# Power.net
KiCad netlist of a schematic drawn in Altium Designer
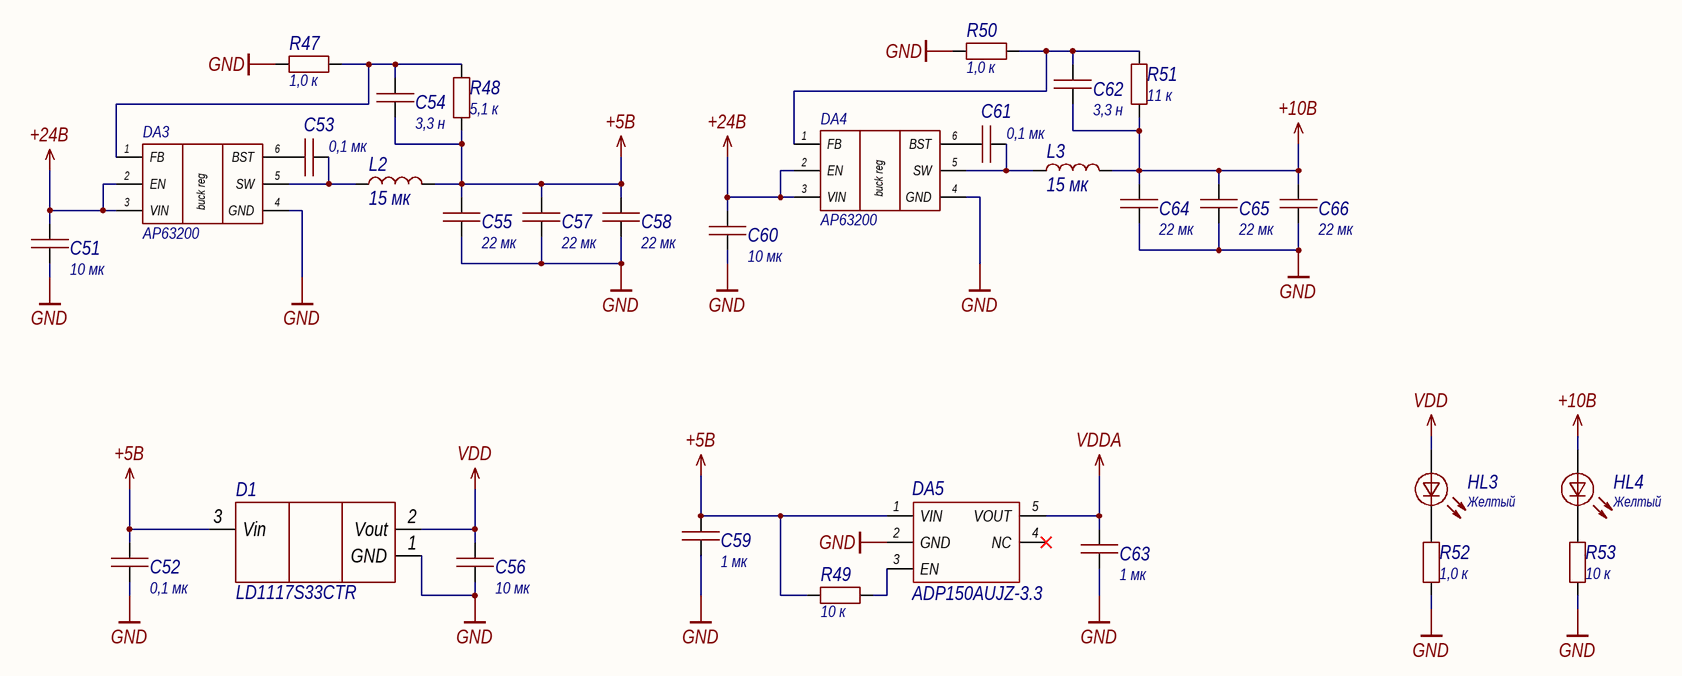
[diagram p0: Power.SchDoc]

(export (version "E")
  (design (tool "Eeschema 10.0.6"))
  (components
    (comp (ref "C51")
      (value "10 мк")
      (footprint "1210C")
      (description "Конденсатор 1210C ёмкостью 10 мк 10%, 35 В, X7R")
      (fields (field (name "PART NUMBER") "Capacitor_10u_10_35V_X7R_1210C") (field (name "TOLERANCE") "10%"))
      (libsource (lib "Hydrolib") (part "Capacitor"))
    )
    (comp (ref "C52")
      (value "0,1 мк")
      (footprint "0603C")
      (description "Конденсатор 0603C ёмкостью 0,1 мк 10%, 50 В, X7R")
      (fields (field (name "PART NUMBER") "Capacitor_0,1u_10_50V_X7R_0603C") (field (name "TOLERANCE") "10%"))
      (libsource (lib "Hydrolib") (part "Capacitor"))
    )
    (comp (ref "C53")
      (value "0,1 мк")
      (footprint "0603C")
      (description "Конденсатор 0603C ёмкостью 0,1 мк 10%, 50 В, X7R")
      (fields (field (name "PART NUMBER") "Capacitor_0,1u_10_50V_X7R_0603C") (field (name "TOLERANCE") "10%"))
      (libsource (lib "Hydrolib") (part "Capacitor"))
    )
    (comp (ref "C54")
      (value "3,3 н")
      (footprint "0603C")
      (description "Конденсатор 0603C ёмкостью 3,3 н 5%, 50 В, NP0")
      (fields
        (field (name "PART NUMBER") "Capacitor_3.3n_5_50V_NP0_0603C")
        (field (name "TOLERANCE") "5%")
        (field (name "АВТОР") "glebmih")
      )
      (libsource (lib "Hydrolib") (part "Capacitor"))
    )
    (comp (ref "C55")
      (value "22 мк")
      (footprint "1210C")
      (description "Конденсатор 1210C ёмкостью 22 мк 10%, 25 В, X7R")
      (fields (field (name "PART NUMBER") "Capacitor_22u_10_25V_X7R_1210C") (field (name "TOLERANCE") "10%"))
      (libsource (lib "Hydrolib") (part "Capacitor"))
    )
    (comp (ref "C56")
      (value "10 мк")
      (footprint "1210C")
      (description "Конденсатор 1210C ёмкостью 10 мк 10%, 35 В, X7R")
      (fields (field (name "PART NUMBER") "Capacitor_10u_10_35V_X7R_1210C") (field (name "TOLERANCE") "10%"))
      (libsource (lib "Hydrolib") (part "Capacitor"))
    )
    (comp (ref "C57")
      (value "22 мк")
      (footprint "1210C")
      (description "Конденсатор 1210C ёмкостью 22 мк 10%, 25 В, X7R")
      (fields (field (name "PART NUMBER") "Capacitor_22u_10_25V_X7R_1210C") (field (name "TOLERANCE") "10%"))
      (libsource (lib "Hydrolib") (part "Capacitor"))
    )
    (comp (ref "C58")
      (value "22 мк")
      (footprint "1210C")
      (description "Конденсатор 1210C ёмкостью 22 мк 10%, 25 В, X7R")
      (fields (field (name "PART NUMBER") "Capacitor_22u_10_25V_X7R_1210C") (field (name "TOLERANCE") "10%"))
      (libsource (lib "Hydrolib") (part "Capacitor"))
    )
    (comp (ref "C59")
      (value "1 мк")
      (footprint "0603C")
      (description "Конденсатор 0603C ёмкостью 1 мк 10%, 25 В, X7R")
      (fields (field (name "PART NUMBER") "Capacitor_1u_10_25V_X7R_0603C") (field (name "TOLERANCE") "10%"))
      (libsource (lib "Hydrolib") (part "Capacitor"))
    )
    (comp (ref "C60")
      (value "10 мк")
      (footprint "1210C")
      (description "Конденсатор 1210C ёмкостью 10 мк 10%, 35 В, X7R")
      (fields (field (name "PART NUMBER") "Capacitor_10u_10_35V_X7R_1210C") (field (name "TOLERANCE") "10%"))
      (libsource (lib "Hydrolib") (part "Capacitor"))
    )
    (comp (ref "C61")
      (value "0,1 мк")
      (footprint "0603C")
      (description "Конденсатор 0603C ёмкостью 0,1 мк 10%, 50 В, X7R")
      (fields (field (name "PART NUMBER") "Capacitor_0,1u_10_50V_X7R_0603C") (field (name "TOLERANCE") "10%"))
      (libsource (lib "Hydrolib") (part "Capacitor"))
    )
    (comp (ref "C62")
      (value "3,3 н")
      (footprint "0603C")
      (description "Конденсатор 0603C ёмкостью 3,3 н 5%, 50 В, NP0")
      (fields
        (field (name "PART NUMBER") "Capacitor_3.3n_5_50V_NP0_0603C")
        (field (name "TOLERANCE") "5%")
        (field (name "АВТОР") "glebmih")
      )
      (libsource (lib "Hydrolib") (part "Capacitor"))
    )
    (comp (ref "C63")
      (value "1 мк")
      (footprint "0603C")
      (description "Конденсатор 0603C ёмкостью 1 мк 10%, 25 В, X7R")
      (fields (field (name "PART NUMBER") "Capacitor_1u_10_25V_X7R_0603C") (field (name "TOLERANCE") "10%"))
      (libsource (lib "Hydrolib") (part "Capacitor"))
    )
    (comp (ref "C64")
      (value "22 мк")
      (footprint "1210C")
      (description "Конденсатор 1210C ёмкостью 22 мк 10%, 25 В, X7R")
      (fields (field (name "PART NUMBER") "Capacitor_22u_10_25V_X7R_1210C") (field (name "TOLERANCE") "10%"))
      (libsource (lib "Hydrolib") (part "Capacitor"))
    )
    (comp (ref "C65")
      (value "22 мк")
      (footprint "1210C")
      (description "Конденсатор 1210C ёмкостью 22 мк 10%, 25 В, X7R")
      (fields (field (name "PART NUMBER") "Capacitor_22u_10_25V_X7R_1210C") (field (name "TOLERANCE") "10%"))
      (libsource (lib "Hydrolib") (part "Capacitor"))
    )
    (comp (ref "C66")
      (value "22 мк")
      (footprint "1210C")
      (description "Конденсатор 1210C ёмкостью 22 мк 10%, 25 В, X7R")
      (fields (field (name "PART NUMBER") "Capacitor_22u_10_25V_X7R_1210C") (field (name "TOLERANCE") "10%"))
      (libsource (lib "Hydrolib") (part "Capacitor"))
    )
    (comp (ref "D1")
      (value "LD1117S33CTR")
      (footprint "SOT223")
      (description "Линейный стабилизатор напряжения")
      (libsource (lib "Hydrolib") (part "LD1117S33CTR"))
    )
    (comp (ref "DA3")
      (value "AP63200")
      (footprint "TSOT26")
      (description "DC-DC понижающий преобразователь, Vin: 3.8 - 40 В, adj, 2 А")
      (libsource (lib "Hydrolib") (part "AP63200"))
    )
    (comp (ref "DA4")
      (value "AP63200")
      (footprint "TSOT26")
      (description "DC-DC понижающий преобразователь, Vin: 3.8 - 40 В, adj, 2 А")
      (libsource (lib "Hydrolib") (part "AP63200"))
    )
    (comp (ref "DA5")
      (value "ADP150AUJZ-3.3")
      (footprint "SOT23-5")
      (description "Стабилизатор напряжения 3.3В 150мА")
      (fields (field (name "АВТОР") "glebmih"))
      (libsource (lib "Hydrolib") (part "ADP150AUJZ-3.3"))
    )
    (comp (ref "HL3")
      (value "Желтый")
      (footprint "0805D")
      (description "Светодиод")
      (fields (field (name "PART NUMBER") "LED"))
      (libsource (lib "Hydrolib") (part "LED"))
    )
    (comp (ref "HL4")
      (value "Желтый")
      (footprint "0805D")
      (description "Светодиод")
      (fields (field (name "PART NUMBER") "LED"))
      (libsource (lib "Hydrolib") (part "LED"))
    )
    (comp (ref "L2")
      (value "15 мк")
      (footprint "SP43")
      (description "Индуктивность на 15 мкГн, номинальный ток 1,3 А")
      (fields (field (name "PART NUMBER") "SP43-150K"))
      (libsource (lib "Hydrolib") (part "Inductance"))
    )
    (comp (ref "L3")
      (value "15 мк")
      (footprint "SP43")
      (description "Индуктивность на 15 мкГн, номинальный ток 1,3 А")
      (fields (field (name "PART NUMBER") "SP43-150K"))
      (libsource (lib "Hydrolib") (part "Inductance"))
    )
    (comp (ref "R47")
      (value "1,0 к")
      (footprint "0603R")
      (description "Резистор номиналом 1,0 кОм 1%")
      (fields (field (name "PART NUMBER") "Resistor_1.0k_1_0603") (field (name "TOLERANCE") "1%"))
      (libsource (lib "") (part "Resistor_1"))
    )
    (comp (ref "R48")
      (value "5,1 к")
      (footprint "0603R")
      (description "Резистор номиналом 5,1 кОм 1%")
      (fields (field (name "PART NUMBER") "Resistor_5.1k_1_0603") (field (name "TOLERANCE") "1%"))
      (libsource (lib "Hydrolib") (part "Resistor"))
    )
    (comp (ref "R49")
      (value "10 к")
      (footprint "0603R")
      (description "Резистор номиналом 10 кОм 1%")
      (fields (field (name "PART NUMBER") "Resistor_10k_1_0603") (field (name "TOLERANCE") "1%"))
      (libsource (lib "") (part "Resistor_2"))
    )
    (comp (ref "R50")
      (value "1,0 к")
      (footprint "0603R")
      (description "Резистор номиналом 1,0 кОм 1%")
      (fields (field (name "PART NUMBER") "Resistor_1.0k_1_0603") (field (name "TOLERANCE") "1%"))
      (libsource (lib "") (part "Resistor_1"))
    )
    (comp (ref "R51")
      (value "11 к")
      (footprint "0603R")
      (description "Резистор номиналом 11 кОм 1%")
      (fields (field (name "PART NUMBER") "Resistor_11k_1_0603") (field (name "TOLERANCE") "1%"))
      (libsource (lib "") (part "Resistor_3"))
    )
    (comp (ref "R52")
      (value "1,0 к")
      (footprint "0603R")
      (description "Резистор номиналом 1,0 кОм 1%")
      (fields (field (name "PART NUMBER") "Resistor_1.0k_1_0603") (field (name "TOLERANCE") "1%"))
      (libsource (lib "") (part "Resistor_3"))
    )
    (comp (ref "R53")
      (value "10 к")
      (footprint "0603R")
      (description "Резистор номиналом 10 кОм 1%")
      (fields (field (name "PART NUMBER") "Resistor_10k_1_0603") (field (name "TOLERANCE") "1%"))
      (libsource (lib "") (part "Resistor_3"))
    )
  )
  (nets
    (net (code "1") (name "+5В") (class "Default")
      (node (ref "C52") (pin "2") (pinfunction "2_2") (pintype "passive"))
      (node (ref "C54") (pin "2") (pinfunction "2_2") (pintype "passive"))
      (node (ref "C55") (pin "2") (pinfunction "2_2") (pintype "passive"))
      (node (ref "C57") (pin "2") (pinfunction "2_2") (pintype "passive"))
      (node (ref "C58") (pin "2") (pinfunction "2_2") (pintype "passive"))
      (node (ref "C59") (pin "2") (pinfunction "2_2") (pintype "passive"))
      (node (ref "D1") (pin "3") (pinfunction "Vin_3") (pintype "passive"))
      (node (ref "DA5") (pin "1") (pinfunction "VIN_1") (pintype "passive"))
      (node (ref "L2") (pin "2") (pinfunction "2_2") (pintype "passive"))
      (node (ref "R48") (pin "2") (pinfunction "2_2") (pintype "passive"))
      (node (ref "R49") (pin "2") (pinfunction "2_2") (pintype "passive"))
    )
    (net (code "2") (name "+10В") (class "Default")
      (node (ref "C62") (pin "2") (pinfunction "2_2") (pintype "passive"))
      (node (ref "C64") (pin "2") (pinfunction "2_2") (pintype "passive"))
      (node (ref "C65") (pin "2") (pinfunction "2_2") (pintype "passive"))
      (node (ref "C66") (pin "2") (pinfunction "2_2") (pintype "passive"))
      (node (ref "HL4") (pin "1") (pinfunction "1_1") (pintype "passive"))
      (node (ref "L3") (pin "2") (pinfunction "2_2") (pintype "passive"))
      (node (ref "R51") (pin "1") (pinfunction "1_1") (pintype "passive"))
    )
    (net (code "3") (name "+24В") (class "Default")
      (node (ref "C51") (pin "2") (pinfunction "2_2") (pintype "passive"))
      (node (ref "C60") (pin "2") (pinfunction "2_2") (pintype "passive"))
      (node (ref "DA3") (pin "2") (pinfunction "EN_2") (pintype "passive"))
      (node (ref "DA3") (pin "3") (pinfunction "VIN_3") (pintype "passive"))
      (node (ref "DA4") (pin "2") (pinfunction "EN_2") (pintype "passive"))
      (node (ref "DA4") (pin "3") (pinfunction "VIN_3") (pintype "passive"))
    )
    (net (code "4") (name "GND") (class "Default")
      (node (ref "C51") (pin "1") (pinfunction "1_1") (pintype "passive"))
      (node (ref "C52") (pin "1") (pinfunction "1_1") (pintype "passive"))
      (node (ref "C55") (pin "1") (pinfunction "1_1") (pintype "passive"))
      (node (ref "C56") (pin "1") (pinfunction "1_1") (pintype "passive"))
      (node (ref "C57") (pin "1") (pinfunction "1_1") (pintype "passive"))
      (node (ref "C58") (pin "1") (pinfunction "1_1") (pintype "passive"))
      (node (ref "C59") (pin "1") (pinfunction "1_1") (pintype "passive"))
      (node (ref "C60") (pin "1") (pinfunction "1_1") (pintype "passive"))
      (node (ref "C63") (pin "1") (pinfunction "1_1") (pintype "passive"))
      (node (ref "C64") (pin "1") (pinfunction "1_1") (pintype "passive"))
      (node (ref "C65") (pin "1") (pinfunction "1_1") (pintype "passive"))
      (node (ref "C66") (pin "1") (pinfunction "1_1") (pintype "passive"))
      (node (ref "D1") (pin "1") (pinfunction "GND_1") (pintype "passive"))
      (node (ref "DA3") (pin "4") (pinfunction "GND_4") (pintype "passive"))
      (node (ref "DA4") (pin "4") (pinfunction "GND_4") (pintype "passive"))
      (node (ref "DA5") (pin "2") (pinfunction "GND_2") (pintype "passive"))
      (node (ref "R47") (pin "1") (pinfunction "1_1") (pintype "passive"))
      (node (ref "R50") (pin "1") (pinfunction "1_1") (pintype "passive"))
      (node (ref "R52") (pin "1") (pinfunction "1_1") (pintype "passive"))
      (node (ref "R53") (pin "1") (pinfunction "1_1") (pintype "passive"))
    )
    (net (code "5") (name "Net-(DA3-BST)") (class "Default")
      (node (ref "C53") (pin "1") (pinfunction "1_1") (pintype "passive"))
      (node (ref "DA3") (pin "6") (pinfunction "BST_6") (pintype "passive"))
    )
    (net (code "6") (name "Net-(DA3-FB)") (class "Default")
      (node (ref "C54") (pin "1") (pinfunction "1_1") (pintype "passive"))
      (node (ref "DA3") (pin "1") (pinfunction "FB_1") (pintype "passive"))
      (node (ref "R47") (pin "2") (pinfunction "2_2") (pintype "passive"))
      (node (ref "R48") (pin "1") (pinfunction "1_1") (pintype "passive"))
    )
    (net (code "7") (name "Net-(DA3-SW)") (class "Default")
      (node (ref "C53") (pin "2") (pinfunction "2_2") (pintype "passive"))
      (node (ref "DA3") (pin "5") (pinfunction "SW_5") (pintype "passive"))
      (node (ref "L2") (pin "1") (pinfunction "1_1") (pintype "passive"))
    )
    (net (code "8") (name "Net-(DA4-BST)") (class "Default")
      (node (ref "C61") (pin "1") (pinfunction "1_1") (pintype "passive"))
      (node (ref "DA4") (pin "6") (pinfunction "BST_6") (pintype "passive"))
    )
    (net (code "9") (name "Net-(DA4-FB)") (class "Default")
      (node (ref "C62") (pin "1") (pinfunction "1_1") (pintype "passive"))
      (node (ref "DA4") (pin "1") (pinfunction "FB_1") (pintype "passive"))
      (node (ref "R50") (pin "2") (pinfunction "2_2") (pintype "passive"))
      (node (ref "R51") (pin "2") (pinfunction "2_2") (pintype "passive"))
    )
    (net (code "10") (name "Net-(DA4-SW)") (class "Default")
      (node (ref "C61") (pin "2") (pinfunction "2_2") (pintype "passive"))
      (node (ref "DA4") (pin "5") (pinfunction "SW_5") (pintype "passive"))
      (node (ref "L3") (pin "1") (pinfunction "1_1") (pintype "passive"))
    )
    (net (code "11") (name "Net-(DA5-EN)") (class "Default")
      (node (ref "DA5") (pin "3") (pinfunction "EN_3") (pintype "passive"))
      (node (ref "R49") (pin "1") (pinfunction "1_1") (pintype "passive"))
    )
    (net (code "12") (name "Net-(HL3-Pad2)") (class "Default")
      (node (ref "HL3") (pin "2") (pinfunction "2_2") (pintype "passive"))
      (node (ref "R52") (pin "2") (pinfunction "2_2") (pintype "passive"))
    )
    (net (code "13") (name "Net-(HL4-Pad2)") (class "Default")
      (node (ref "HL4") (pin "2") (pinfunction "2_2") (pintype "passive"))
      (node (ref "R53") (pin "2") (pinfunction "2_2") (pintype "passive"))
    )
    (net (code "14") (name "VDD") (class "Default")
      (node (ref "C56") (pin "2") (pinfunction "2_2") (pintype "passive"))
      (node (ref "D1") (pin "2") (pinfunction "Vout_2") (pintype "passive"))
      (node (ref "HL3") (pin "1") (pinfunction "1_1") (pintype "passive"))
    )
    (net (code "15") (name "VDDA") (class "Default")
      (node (ref "C63") (pin "2") (pinfunction "2_2") (pintype "passive"))
      (node (ref "DA5") (pin "5") (pinfunction "VOUT_5") (pintype "passive"))
    )
    (net (code "16") (name "unconnected-(DA5-NC-Pad4)") (class "Default")
      (node (ref "DA5") (pin "4") (pinfunction "NC_4") (pintype "passive+no_connect"))
    )
  )
)
